# compSensorMB.net
KiCad netlist of a schematic drawn in EasyEDA Pro
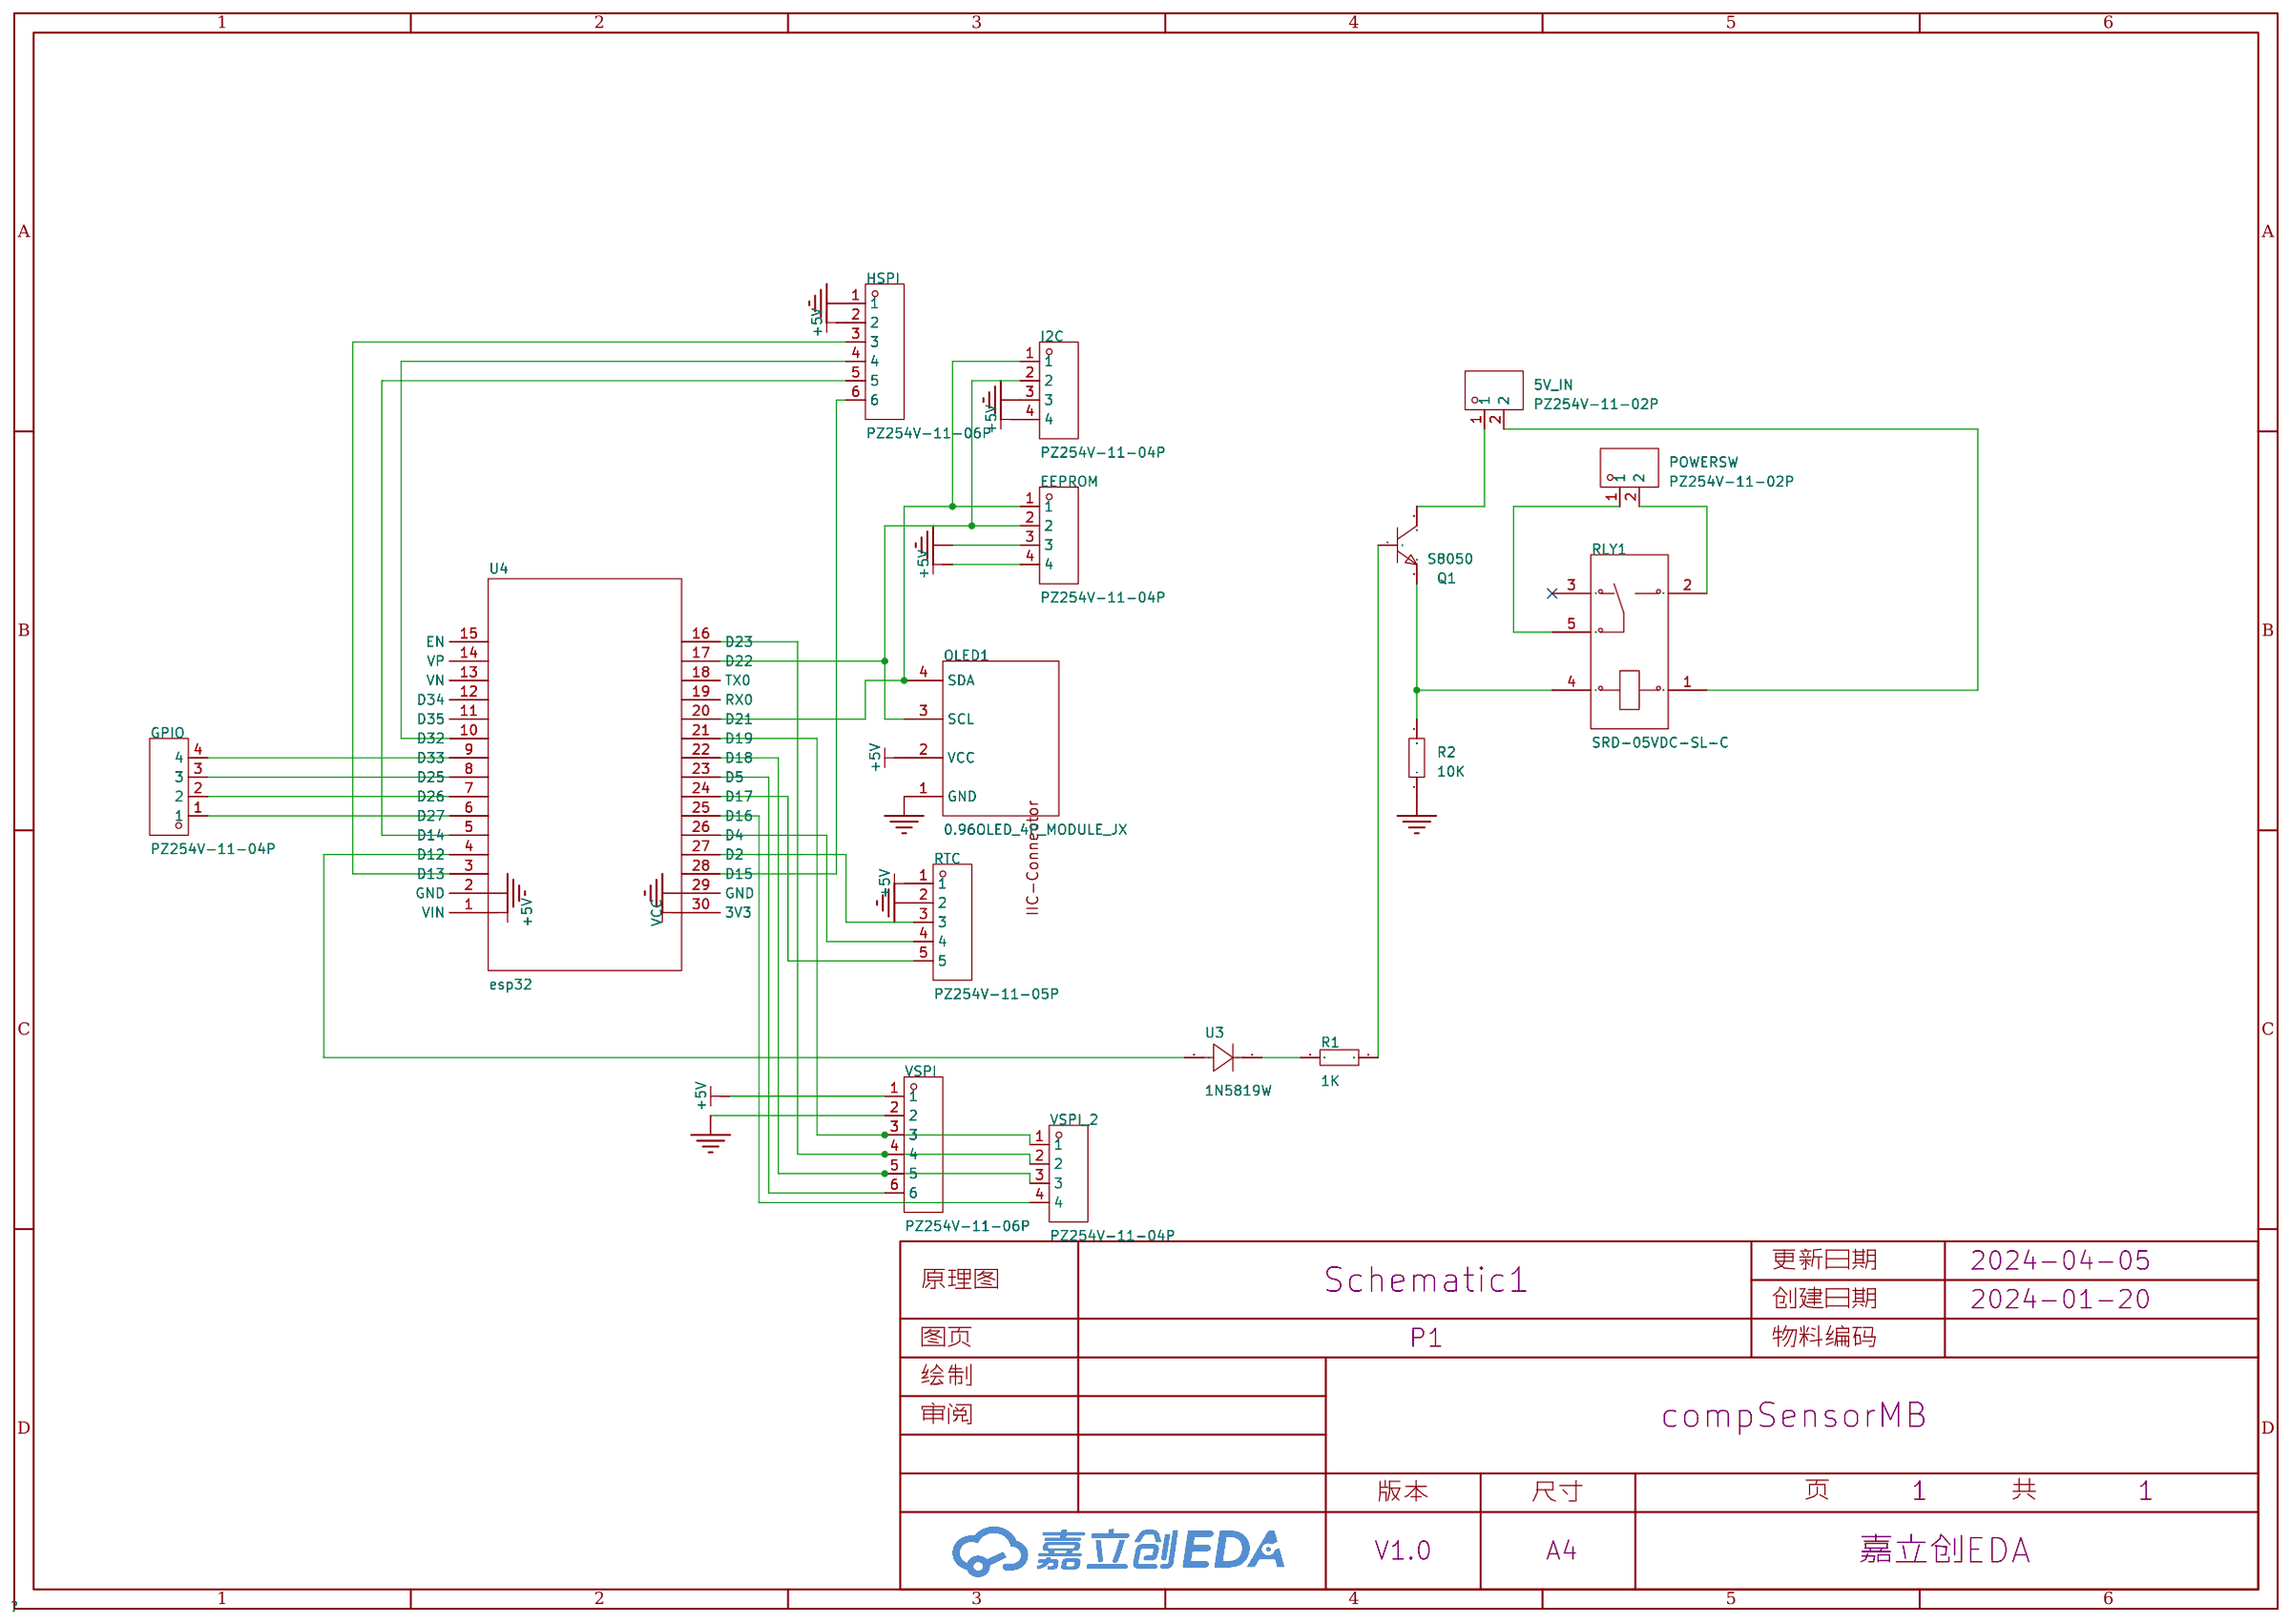
[diagram p0: schematic sheet]

(export (version "E")
  (design (tool "Eeschema 10.0.6"))
  (components
    (comp (ref "5V_IN")
      (value "PZ254V-11-02P")
      (footprint "easyedapro:HDR-TH_2P-P2.54-V-M")
      (fields (field (name "Manufacturer") "XFCN(兴飞)"))
      (libsource (lib "easyedapro") (part "PZ254V-11-02P"))
    )
    (comp (ref "EEPROM")
      (value "PZ254V-11-04P")
      (footprint "easyedapro:HDR-TH_4P-P2.54-V-M")
      (fields (field (name "Manufacturer") "XFCN(兴飞)"))
      (libsource (lib "easyedapro") (part "PZ254V-11-04P_C2691448"))
    )
    (comp (ref "GPIO")
      (value "PZ254V-11-04P")
      (footprint "easyedapro:HDR-TH_4P-P2.54-V-M")
      (fields (field (name "Manufacturer") "XFCN(兴飞)"))
      (libsource (lib "easyedapro") (part "PZ254V-11-04P_C2691448"))
    )
    (comp (ref "HSPI")
      (value "PZ254V-11-06P")
      (footprint "easyedapro:HDR-TH_6P-P2.54-V-M")
      (fields (field (name "Manufacturer") "XFCN(兴飞)"))
      (libsource (lib "easyedapro") (part "PZ254V-11-06P"))
    )
    (comp (ref "I2C")
      (value "PZ254V-11-04P")
      (footprint "easyedapro:HDR-TH_4P-P2.54-V-M")
      (fields (field (name "Manufacturer") "XFCN(兴飞)"))
      (libsource (lib "easyedapro") (part "PZ254V-11-04P_C2691448"))
    )
    (comp (ref "OLED1")
      (value "0.96OLED_4P_MODULE_JX")
      (footprint "easyedapro:0.96OLED_4P")
      (libsource (lib "easyedapro") (part "0.96OLED_4P_MODULE_JX"))
    )
    (comp (ref "POWERSW")
      (value "PZ254V-11-02P")
      (footprint "easyedapro:HDR-TH_2P-P2.54-V-M")
      (fields (field (name "Manufacturer") "XFCN(兴飞)"))
      (libsource (lib "easyedapro") (part "PZ254V-11-02P"))
    )
    (comp (ref "Q1")
      (value "S8050")
      (footprint "easyedapro:SOT-23-3_L2.9-W1.3-P1.90-LS2.4-BR")
      (description "晶体管类型:NPN;集电极电流(Ic):500mA;集射极击穿电压(Vceo):25V;功率(Pd):300mW;")
      (fields (field (name "Manufacturer") "YONGYUTAI(永裕泰)"))
      (libsource (lib "easyedapro") (part "S8050_C2891804"))
    )
    (comp (ref "R1") (value "1K") (footprint "easyedapro:R0603") (libsource (lib "easyedapro") (part "电阻")))
    (comp (ref "R2") (value "10K") (footprint "easyedapro:R0603") (libsource (lib "easyedapro") (part "电阻")))
    (comp (ref "RLY1")
      (value "SRD-05VDC-SL-C")
      (footprint "easyedapro:RELAY-TH_SRD-XXVDC-XL-C")
      (description "线圈电压:5V;触点形式:一组转换:1C(单刀双掷-转换);触点容量(电阻负载):-;最大切换电压:250V@AC;最大切换电流:15A;")
      (fields (field (name "Manufacturer") "松乐"))
      (libsource (lib "easyedapro") (part "SRD-05VDC-SL-C"))
    )
    (comp (ref "RTC")
      (value "PZ254V-11-05P")
      (footprint "easyedapro:HDR-TH_5P-P2.54-V-M")
      (fields (field (name "Manufacturer") "XFCN(兴飞)"))
      (libsource (lib "easyedapro") (part "PZ254V-11-05P"))
    )
    (comp (ref "U3")
      (value "1N5819W")
      (footprint "easyedapro:SMA_L4.3-W2.6-LS5.1-RD")
      (fields (field (name "Manufacturer") "JSMSEMI(杰盛微)"))
      (libsource (lib "easyedapro") (part "1N4007_C9900004759"))
    )
    (comp (ref "U4")
      (value "esp32")
      (footprint "easyedapro:esp32")
      (libsource (lib "easyedapro") (part "esp32"))
    )
    (comp (ref "VSPI")
      (value "PZ254V-11-06P")
      (footprint "easyedapro:HDR-TH_6P-P2.54-V-M")
      (fields (field (name "Manufacturer") "XFCN(兴飞)"))
      (libsource (lib "easyedapro") (part "PZ254V-11-06P"))
    )
    (comp (ref "VSPI_2")
      (value "PZ254V-11-04P")
      (footprint "easyedapro:HDR-TH_4P-P2.54-V-M")
      (fields (field (name "Manufacturer") "XFCN(兴飞)"))
      (libsource (lib "easyedapro") (part "PZ254V-11-04P_C2691448"))
    )
  )
  (nets
    (net (code "1") (name "+5V") (class "Default")
      (node (ref "EEPROM") (pin "4") (pinfunction "4_4") (pintype "unspecified"))
      (node (ref "HSPI") (pin "2") (pinfunction "2_2") (pintype "unspecified"))
      (node (ref "I2C") (pin "4") (pinfunction "4_4") (pintype "unspecified"))
      (node (ref "OLED1") (pin "2") (pinfunction "VCC_2") (pintype "input"))
      (node (ref "RTC") (pin "1") (pinfunction "1_1") (pintype "unspecified"))
      (node (ref "U4") (pin "1") (pinfunction "VIN_1") (pintype "input"))
      (node (ref "VSPI") (pin "1") (pinfunction "1_1") (pintype "unspecified"))
    )
    (net (code "2") (name "GND") (class "Default")
      (node (ref "EEPROM") (pin "3") (pinfunction "3_3") (pintype "unspecified"))
      (node (ref "HSPI") (pin "1") (pinfunction "1_1") (pintype "unspecified"))
      (node (ref "I2C") (pin "3") (pinfunction "3_3") (pintype "unspecified"))
      (node (ref "OLED1") (pin "1") (pinfunction "GND_1") (pintype "input"))
      (node (ref "R2") (pin "1") (pinfunction "1_1") (pintype "input"))
      (node (ref "RTC") (pin "2") (pinfunction "2_2") (pintype "unspecified"))
      (node (ref "U4") (pin "2") (pinfunction "GND_2") (pintype "input"))
      (node (ref "U4") (pin "29") (pinfunction "GND_29") (pintype "input"))
      (node (ref "VSPI") (pin "2") (pinfunction "2_2") (pintype "unspecified"))
    )
    (net (code "3") (name "Net-(5V_IN-Pad2)") (class "Default")
      (node (ref "5V_IN") (pin "2") (pinfunction "2_2") (pintype "unspecified"))
      (node (ref "RLY1") (pin "1") (pinfunction "1_1") (pintype "input"))
    )
    (net (code "4") (name "Net-(OLED1-SCL)") (class "Default")
      (node (ref "EEPROM") (pin "2") (pinfunction "2_2") (pintype "unspecified"))
      (node (ref "I2C") (pin "2") (pinfunction "2_2") (pintype "unspecified"))
      (node (ref "OLED1") (pin "3") (pinfunction "SCL_3") (pintype "input"))
      (node (ref "U4") (pin "17") (pinfunction "D22_17") (pintype "input"))
    )
    (net (code "5") (name "Net-(OLED1-SDA)") (class "Default")
      (node (ref "EEPROM") (pin "1") (pinfunction "1_1") (pintype "unspecified"))
      (node (ref "I2C") (pin "1") (pinfunction "1_1") (pintype "unspecified"))
      (node (ref "OLED1") (pin "4") (pinfunction "SDA_4") (pintype "input"))
      (node (ref "U4") (pin "20") (pinfunction "D21_20") (pintype "input"))
    )
    (net (code "6") (name "Net-(POWERSW-Pad1)") (class "Default")
      (node (ref "POWERSW") (pin "1") (pinfunction "1_1") (pintype "unspecified"))
      (node (ref "RLY1") (pin "5") (pinfunction "5_5") (pintype "input"))
    )
    (net (code "7") (name "Net-(POWERSW-Pad2)") (class "Default")
      (node (ref "POWERSW") (pin "2") (pinfunction "2_2") (pintype "unspecified"))
      (node (ref "RLY1") (pin "2") (pinfunction "2_2") (pintype "input"))
    )
    (net (code "8") (name "Net-(Q1-B)") (class "Default")
      (node (ref "Q1") (pin "1") (pinfunction "B_1") (pintype "unspecified"))
      (node (ref "R1") (pin "2") (pinfunction "2_2") (pintype "input"))
    )
    (net (code "9") (name "Net-(Q1-C)") (class "Default")
      (node (ref "5V_IN") (pin "1") (pinfunction "1_1") (pintype "unspecified"))
      (node (ref "Q1") (pin "3") (pinfunction "C_3") (pintype "unspecified"))
    )
    (net (code "10") (name "Net-(Q1-E)") (class "Default")
      (node (ref "Q1") (pin "2") (pinfunction "E_2") (pintype "unspecified"))
      (node (ref "R2") (pin "2") (pinfunction "2_2") (pintype "input"))
      (node (ref "RLY1") (pin "4") (pinfunction "4_4") (pintype "input"))
    )
    (net (code "11") (name "Net-(U3-A)") (class "Default")
      (node (ref "U3") (pin "2") (pinfunction "A_2") (pintype "input"))
      (node (ref "U4") (pin "4") (pinfunction "D12_4") (pintype "input"))
    )
    (net (code "12") (name "Net-(U3-K)") (class "Default")
      (node (ref "R1") (pin "1") (pinfunction "1_1") (pintype "input"))
      (node (ref "U3") (pin "1") (pinfunction "K_1") (pintype "input"))
    )
    (net (code "13") (name "Net-(U4-D2)") (class "Default")
      (node (ref "RTC") (pin "3") (pinfunction "3_3") (pintype "unspecified"))
      (node (ref "U4") (pin "27") (pinfunction "D2_27") (pintype "input"))
    )
    (net (code "14") (name "Net-(U4-D4)") (class "Default")
      (node (ref "RTC") (pin "4") (pinfunction "4_4") (pintype "unspecified"))
      (node (ref "U4") (pin "26") (pinfunction "D4_26") (pintype "input"))
    )
    (net (code "15") (name "Net-(U4-D5)") (class "Default")
      (node (ref "U4") (pin "23") (pinfunction "D5_23") (pintype "input"))
      (node (ref "VSPI") (pin "6") (pinfunction "6_6") (pintype "unspecified"))
    )
    (net (code "16") (name "Net-(U4-D13)") (class "Default")
      (node (ref "HSPI") (pin "3") (pinfunction "3_3") (pintype "unspecified"))
      (node (ref "U4") (pin "3") (pinfunction "D13_3") (pintype "input"))
    )
    (net (code "17") (name "Net-(U4-D14)") (class "Default")
      (node (ref "HSPI") (pin "5") (pinfunction "5_5") (pintype "unspecified"))
      (node (ref "U4") (pin "5") (pinfunction "D14_5") (pintype "input"))
    )
    (net (code "18") (name "Net-(U4-D15)") (class "Default")
      (node (ref "HSPI") (pin "6") (pinfunction "6_6") (pintype "unspecified"))
      (node (ref "U4") (pin "28") (pinfunction "D15_28") (pintype "input"))
    )
    (net (code "19") (name "Net-(U4-D16)") (class "Default")
      (node (ref "U4") (pin "25") (pinfunction "D16_25") (pintype "input"))
      (node (ref "VSPI_2") (pin "4") (pinfunction "4_4") (pintype "unspecified"))
    )
    (net (code "20") (name "Net-(U4-D17)") (class "Default")
      (node (ref "RTC") (pin "5") (pinfunction "5_5") (pintype "unspecified"))
      (node (ref "U4") (pin "24") (pinfunction "D17_24") (pintype "input"))
    )
    (net (code "21") (name "Net-(U4-D18)") (class "Default")
      (node (ref "U4") (pin "22") (pinfunction "D18_22") (pintype "input"))
      (node (ref "VSPI") (pin "5") (pinfunction "5_5") (pintype "unspecified"))
      (node (ref "VSPI_2") (pin "3") (pinfunction "3_3") (pintype "unspecified"))
    )
    (net (code "22") (name "Net-(U4-D19)") (class "Default")
      (node (ref "U4") (pin "21") (pinfunction "D19_21") (pintype "input"))
      (node (ref "VSPI") (pin "3") (pinfunction "3_3") (pintype "unspecified"))
      (node (ref "VSPI_2") (pin "1") (pinfunction "1_1") (pintype "unspecified"))
    )
    (net (code "23") (name "Net-(U4-D23)") (class "Default")
      (node (ref "U4") (pin "16") (pinfunction "D23_16") (pintype "input"))
      (node (ref "VSPI") (pin "4") (pinfunction "4_4") (pintype "unspecified"))
      (node (ref "VSPI_2") (pin "2") (pinfunction "2_2") (pintype "unspecified"))
    )
    (net (code "24") (name "Net-(U4-D25)") (class "Default")
      (node (ref "GPIO") (pin "3") (pinfunction "3_3") (pintype "unspecified"))
      (node (ref "U4") (pin "8") (pinfunction "D25_8") (pintype "input"))
    )
    (net (code "25") (name "Net-(U4-D26)") (class "Default")
      (node (ref "GPIO") (pin "2") (pinfunction "2_2") (pintype "unspecified"))
      (node (ref "U4") (pin "7") (pinfunction "D26_7") (pintype "input"))
    )
    (net (code "26") (name "Net-(U4-D27)") (class "Default")
      (node (ref "GPIO") (pin "1") (pinfunction "1_1") (pintype "unspecified"))
      (node (ref "U4") (pin "6") (pinfunction "D27_6") (pintype "input"))
    )
    (net (code "27") (name "Net-(U4-D32)") (class "Default")
      (node (ref "HSPI") (pin "4") (pinfunction "4_4") (pintype "unspecified"))
      (node (ref "U4") (pin "10") (pinfunction "D32_10") (pintype "input"))
    )
    (net (code "28") (name "Net-(U4-D33)") (class "Default")
      (node (ref "GPIO") (pin "4") (pinfunction "4_4") (pintype "unspecified"))
      (node (ref "U4") (pin "9") (pinfunction "D33_9") (pintype "input"))
    )
    (net (code "29") (name "VCC") (class "Default")
      (node (ref "U4") (pin "30") (pinfunction "3V3_30") (pintype "input"))
    )
    (net (code "30") (name "unconnected-(RLY1-Pad3)") (class "Default")
      (node (ref "RLY1") (pin "3") (pinfunction "3_3") (pintype "input+no_connect"))
    )
    (net (code "31") (name "unconnected-(U4-D34-Pad12)") (class "Default")
      (node (ref "U4") (pin "12") (pinfunction "D34_12") (pintype "input"))
    )
    (net (code "32") (name "unconnected-(U4-D35-Pad11)") (class "Default")
      (node (ref "U4") (pin "11") (pinfunction "D35_11") (pintype "input"))
    )
    (net (code "33") (name "unconnected-(U4-EN-Pad15)") (class "Default")
      (node (ref "U4") (pin "15") (pinfunction "EN_15") (pintype "input"))
    )
    (net (code "34") (name "unconnected-(U4-RX0-Pad19)") (class "Default")
      (node (ref "U4") (pin "19") (pinfunction "RX0_19") (pintype "input"))
    )
    (net (code "35") (name "unconnected-(U4-TX0-Pad18)") (class "Default")
      (node (ref "U4") (pin "18") (pinfunction "TX0_18") (pintype "input"))
    )
    (net (code "36") (name "unconnected-(U4-VN-Pad13)") (class "Default")
      (node (ref "U4") (pin "13") (pinfunction "VN_13") (pintype "input"))
    )
    (net (code "37") (name "unconnected-(U4-VP-Pad14)") (class "Default")
      (node (ref "U4") (pin "14") (pinfunction "VP_14") (pintype "input"))
    )
  )
)
